# cSLIM_display.net
KiCad netlist of a schematic drawn in Altium Designer
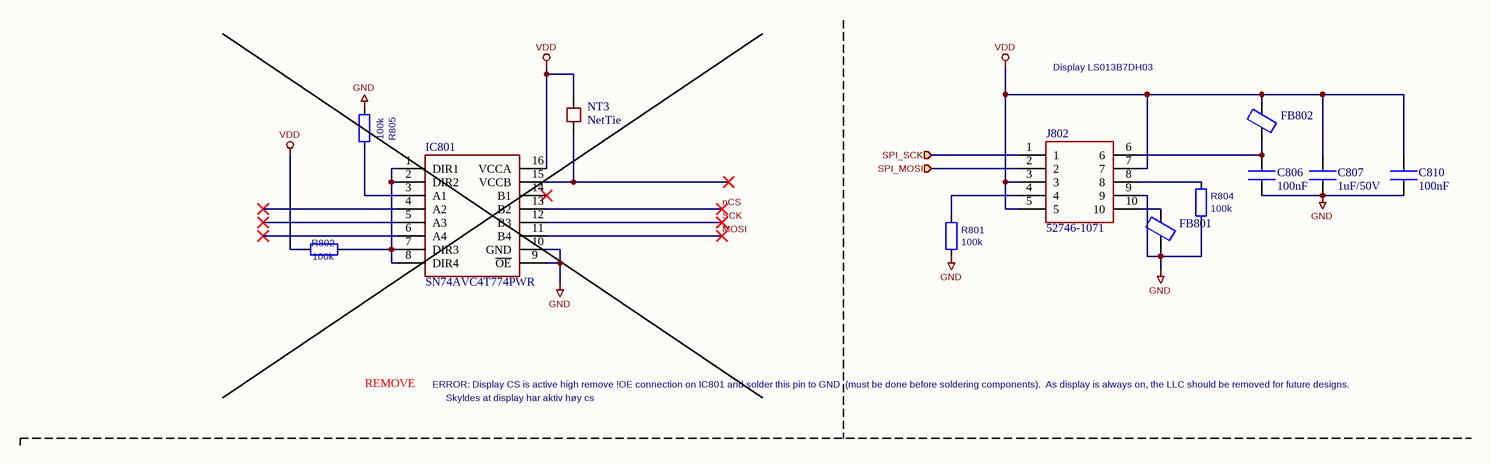
[diagram p0: cSLIM_display.SchDoc]

(export (version "E")
  (design (tool "Eeschema 10.0.6"))
  (components
    (comp (ref "C806")
      (value "100nF")
      (footprint "cSLIM-SA:CAPC1608X90N")
      (description "Capacitor")
      (fields
        (field (name "MANUFACTURER_PART_NUMBER") "06033G104ZAT2A")
        (field (name "MOUSER PART NUMBER") "581-06033G104Z")
      )
      (libsource (lib "cSLIM-SA") (part "C"))
    )
    (comp (ref "C807")
      (value "1uF/50V")
      (footprint "cSLIM-SA:CAPC1608X90N")
      (description "Capacitor")
      (fields
        (field (name "MANUFACTURER_PART_NUMBER") "06033G104ZAT2A")
        (field (name "MOUSER PART NUMBER") "581-06033G104Z")
      )
      (libsource (lib "cSLIM-SA") (part "C"))
    )
    (comp (ref "C810")
      (value "100nF")
      (footprint "cSLIM-SA:CAPC1608X90N")
      (description "Capacitor")
      (fields
        (field (name "MANUFACTURER_PART_NUMBER") "06033G104ZAT2A")
        (field (name "MOUSER PART NUMBER") "581-06033G104Z")
      )
      (libsource (lib "cSLIM-SA") (part "C"))
    )
    (comp (ref "FB801")
      (value "Ferrite_Bead")
      (footprint "CAPC1608X90N")
      (libsource (lib "cSLIM-SA") (part "Ferrite_Bead"))
    )
    (comp (ref "FB802")
      (value "Ferrite_Bead")
      (footprint "CAPC1608X90N")
      (libsource (lib "cSLIM-SA") (part "Ferrite_Bead"))
    )
    (comp (ref "IC801")
      (value "SN74AVC4T774PWR")
      (footprint "cSLIM-SA:SOP65P640X120-16N")
      (description "Integrated Circuit")
      (fields (field (name "MOUSER PART NUMBER") "595-SN74AVC4T774PWR"))
      (libsource (lib "cSLIM-SA") (part "SN74AVC4T774PWR"))
    )
    (comp (ref "J802")
      (value "52746-1071")
      (footprint "cSLIM-SA:52746-1071")
      (description "Connector")
      (fields (field (name "MOUSER PART NUMBER") "538-52746-1071"))
      (libsource (lib "cSLIM-SA") (part "52746-1071"))
    )
    (comp (ref "NT3") (value "NetTie") (footprint "NETTIE_FP") (libsource (lib "cSLIM-SA") (part "NetTie")))
    (comp (ref "R801") (value "100k") (footprint "RESC1608X55N") (libsource (lib "cSLIM-SA") (part "R")))
    (comp (ref "R802") (value "100k") (footprint "R_0805_2012Metric") (libsource (lib "") (part "R_1")))
    (comp (ref "R804") (value "100k") (footprint "RESC1608X55N") (libsource (lib "cSLIM-SA") (part "R")))
    (comp (ref "R805") (value "100k") (footprint "R_0805_2012Metric") (libsource (lib "Device") (part "R")))
  )
  (nets
    (net (code "1") (name "/MOSI") (class "Default")
      (node (ref "IC801") (pin "11") (pinfunction "B4_11") (pintype "passive+no_connect"))
    )
    (net (code "2") (name "/SCK") (class "Default")
      (node (ref "IC801") (pin "12") (pinfunction "B3_12") (pintype "passive+no_connect"))
    )
    (net (code "3") (name "/SPI_MOSI") (class "Default")
      (node (ref "J802") (pin "2") (pinfunction "2_2") (pintype "passive"))
    )
    (net (code "4") (name "/SPI_SCK") (class "Default")
      (node (ref "J802") (pin "1") (pinfunction "1_1") (pintype "passive"))
    )
    (net (code "5") (name "/nCS") (class "Default")
      (node (ref "IC801") (pin "13") (pinfunction "B2_13") (pintype "passive+no_connect"))
    )
    (net (code "6") (name "GND") (class "Default")
      (node (ref "C806") (pin "2") (pinfunction "2_2") (pintype "passive"))
      (node (ref "C807") (pin "2") (pinfunction "2_2") (pintype "passive"))
      (node (ref "C810") (pin "2") (pinfunction "2_2") (pintype "passive"))
      (node (ref "FB801") (pin "2") (pinfunction "2_2") (pintype "passive"))
      (node (ref "IC801") (pin "10") (pinfunction "GND_10") (pintype "passive"))
      (node (ref "IC801") (pin "9") (pinfunction "~{OE}_9") (pintype "passive"))
      (node (ref "J802") (pin "9") (pinfunction "9_9") (pintype "passive"))
      (node (ref "R801") (pin "2") (pinfunction "2_2") (pintype "passive"))
      (node (ref "R804") (pin "2") (pinfunction "2_2") (pintype "passive"))
      (node (ref "R805") (pin "2") (pinfunction "2_2") (pintype "passive"))
    )
    (net (code "7") (name "Net-(C806-Pad1)") (class "Default")
      (node (ref "C806") (pin "1") (pinfunction "1_1") (pintype "passive"))
      (node (ref "FB802") (pin "2") (pinfunction "2_2") (pintype "passive"))
      (node (ref "J802") (pin "6") (pinfunction "6_6") (pintype "passive"))
    )
    (net (code "8") (name "Net-(FB801-Pad1)") (class "Default")
      (node (ref "FB801") (pin "1") (pinfunction "1_1") (pintype "passive"))
      (node (ref "J802") (pin "10") (pinfunction "10_10") (pintype "passive"))
    )
    (net (code "9") (name "Net-(IC801-A1)") (class "Default")
      (node (ref "IC801") (pin "3") (pinfunction "A1_3") (pintype "passive"))
      (node (ref "R805") (pin "1") (pinfunction "1_1") (pintype "passive"))
    )
    (net (code "10") (name "Net-(IC801-DIR1)") (class "Default")
      (node (ref "IC801") (pin "1") (pinfunction "DIR1_1") (pintype "passive"))
      (node (ref "IC801") (pin "2") (pinfunction "DIR2_2") (pintype "passive"))
      (node (ref "IC801") (pin "7") (pinfunction "DIR3_7") (pintype "passive"))
      (node (ref "IC801") (pin "8") (pinfunction "DIR4_8") (pintype "passive"))
      (node (ref "R802") (pin "1") (pinfunction "1_1") (pintype "passive"))
    )
    (net (code "11") (name "Net-(J802-Pad4)") (class "Default")
      (node (ref "J802") (pin "4") (pinfunction "4_4") (pintype "passive"))
      (node (ref "R801") (pin "1") (pinfunction "1_1") (pintype "passive"))
    )
    (net (code "12") (name "Net-(J802-Pad8)") (class "Default")
      (node (ref "J802") (pin "8") (pinfunction "8_8") (pintype "passive"))
      (node (ref "R804") (pin "1") (pinfunction "1_1") (pintype "passive"))
    )
    (net (code "13") (name "VDD") (class "Default")
      (node (ref "C807") (pin "1") (pinfunction "1_1") (pintype "passive"))
      (node (ref "C810") (pin "1") (pinfunction "1_1") (pintype "passive"))
      (node (ref "FB802") (pin "1") (pinfunction "1_1") (pintype "passive"))
      (node (ref "IC801") (pin "16") (pinfunction "VCCA_16") (pintype "passive"))
      (node (ref "J802") (pin "3") (pinfunction "3_3") (pintype "passive"))
      (node (ref "J802") (pin "5") (pinfunction "5_5") (pintype "passive"))
      (node (ref "J802") (pin "7") (pinfunction "7_7") (pintype "passive"))
      (node (ref "R802") (pin "2") (pinfunction "2_2") (pintype "passive"))
    )
    (net (code "14") (name "unconnected-(IC801-A2-Pad4)") (class "Default")
      (node (ref "IC801") (pin "4") (pinfunction "A2_4") (pintype "passive+no_connect"))
    )
    (net (code "15") (name "unconnected-(IC801-A3-Pad5)") (class "Default")
      (node (ref "IC801") (pin "5") (pinfunction "A3_5") (pintype "passive+no_connect"))
    )
    (net (code "16") (name "unconnected-(IC801-A4-Pad6)") (class "Default")
      (node (ref "IC801") (pin "6") (pinfunction "A4_6") (pintype "passive+no_connect"))
    )
    (net (code "17") (name "unconnected-(IC801-B1-Pad14)") (class "Default")
      (node (ref "IC801") (pin "14") (pinfunction "B1_14") (pintype "passive+no_connect"))
    )
    (net (code "18") (name "unconnected-(IC801-VCCB-Pad15)") (class "Default")
      (node (ref "IC801") (pin "15") (pinfunction "VCCB_15") (pintype "passive+no_connect"))
    )
    (net (code "19") (name "unconnected-(NT3-Pad1)") (class "Default")
      (node (ref "NT3") (pin "1") (pintype "passive"))
    )
    (net (code "20") (name "unconnected-(NT3-Pad2)") (class "Default")
      (node (ref "NT3") (pin "2") (pintype "passive"))
    )
  )
)
